# PowerStage.net
KiCad netlist of a schematic drawn in Altium Designer
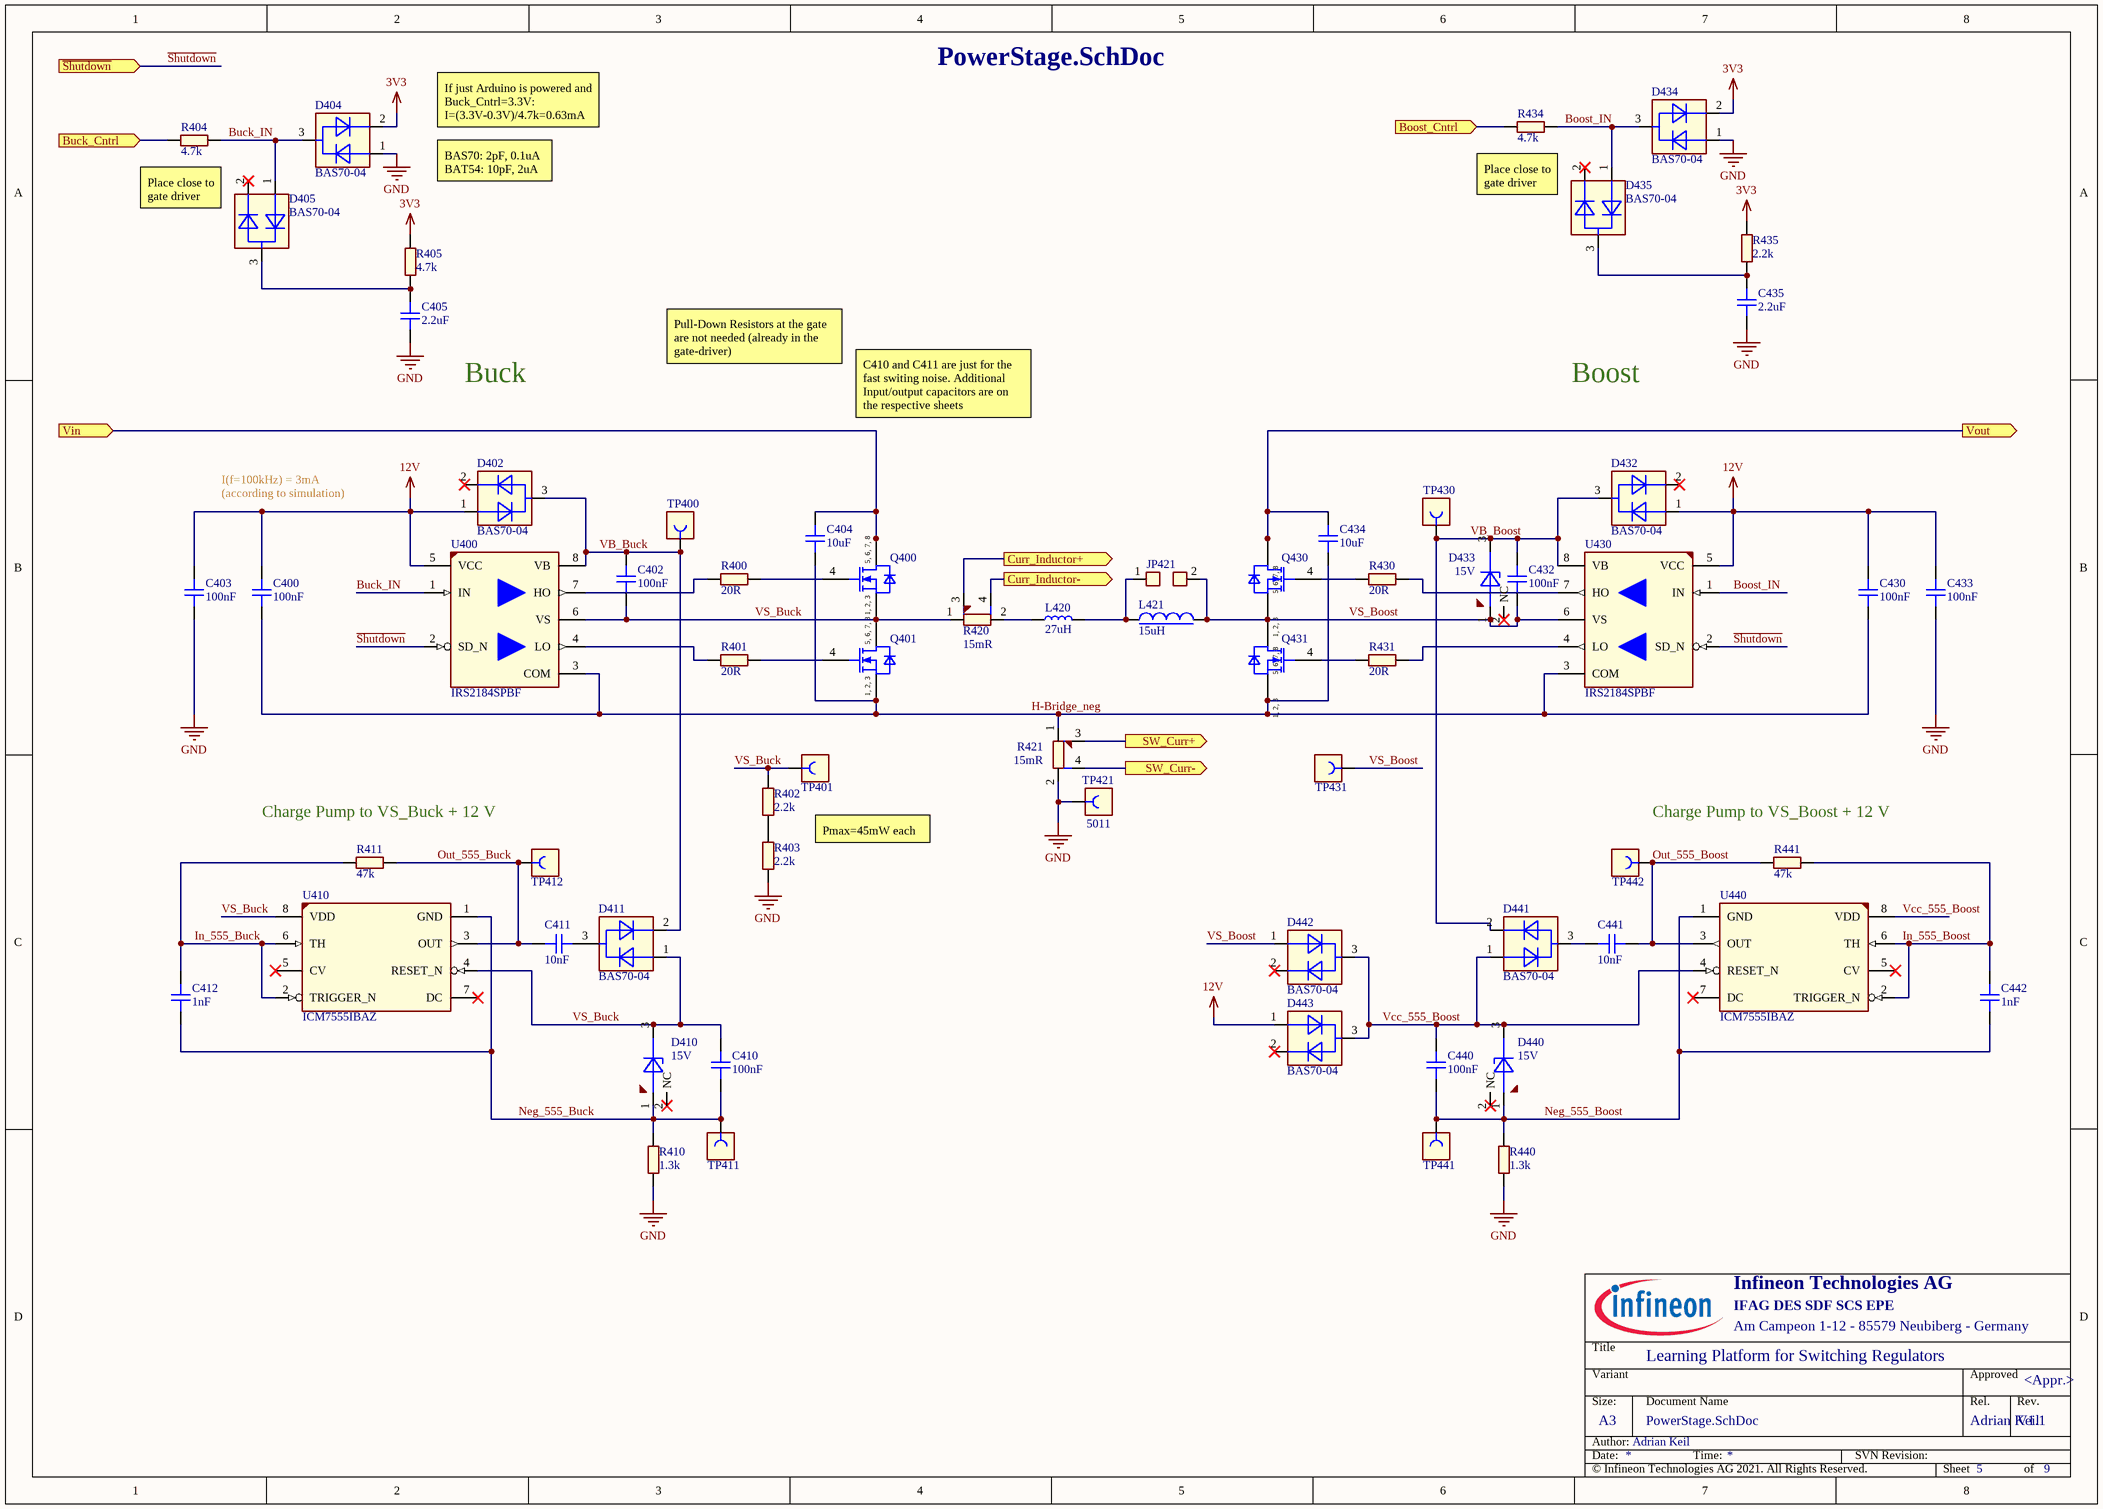
[diagram p0: PowerStage.SchDoc]

(export (version "E")
  (design (tool "Eeschema 10.0.6"))
  (components
    (comp (ref "C400")
      (value "100nF")
      (footprint "CAPC1608X90N-2")
      (description "CAP / CERA / 100nF / 50V / 10% / X7R (EIA) / -55°C to 125°C / 0603 / SMD / -")
      (fields (field (name "MANUFACTURER") "AVX"))
      (libsource (lib "PCBLibraryData") (part "CAP-SGL-STD-02P_00000001"))
    )
    (comp (ref "C402")
      (value "100nF")
      (footprint "CAPC1608X90N-2")
      (description "CAP / CERA / 100nF / 50V / 10% / X7R (EIA) / -55°C to 125°C / 0603 / SMD / -")
      (fields (field (name "MANUFACTURER") "AVX"))
      (libsource (lib "PCBLibraryData") (part "CAP-SGL-STD-02P_00000001"))
    )
    (comp (ref "C403")
      (value "100nF")
      (footprint "CAPC1608X90N-2")
      (description "CAP / CERA / 100nF / 50V / 10% / X7R (EIA) / -55°C to 125°C / 0603 / SMD / -")
      (fields (field (name "MANUFACTURER") "AVX"))
      (libsource (lib "PCBLibraryData") (part "CAP-SGL-STD-02P_00000001"))
    )
    (comp (ref "C404")
      (value "10uF")
      (footprint "CAPC3216X190N-1")
      (description "CAP / CERA / 10uF / 50V / 20% / X5R (EIA) / -55°C to 85°C / 1206 (3216) / SMD / -")
      (fields (field (name "MANUFACTURER") "Taiyo Yuden"))
      (libsource (lib "PCBLibraryData") (part "CAP-SGL-STD-02P_00000001"))
    )
    (comp (ref "C405")
      (value "2.2uF")
      (footprint "CAPC1608X90N-3")
      (description "CAP / CERA / 2.2uF / 25V / 10% / X5R (EIA) / -55°C to 85°C / 0603(1608) / SMD / -")
      (fields (field (name "LEGACY PARTNUMBER") "CAP01010924") (field (name "MANUFACTURER") "MuRata"))
      (libsource (lib "PCBLibraryData") (part "CAP-SGL-STD-02P_00000001"))
    )
    (comp (ref "C410")
      (value "100nF")
      (footprint "CAPC1608X90N-2")
      (description "CAP / CERA / 100nF / 50V / 10% / X7R (EIA) / -55°C to 125°C / 0603 / SMD / -")
      (fields (field (name "MANUFACTURER") "AVX"))
      (libsource (lib "PCBLibraryData") (part "CAP-SGL-STD-02P_00000001"))
    )
    (comp (ref "C411")
      (value "10nF")
      (footprint "CAPC1608X90N-4")
      (description "CAP / CERA / 10nF / 50V / 10% / X8R (EIA) / -55°C to 150°C / 0603(1608) / SMD / -")
      (fields
        (field (name "LEGACY PARTNUMBER") "CAP01010834")
        (field (name "MANUFACTURER") "TDK Corporation")
      )
      (libsource (lib "PCBLibraryData") (part "CAP-SGL-STD-02P_00000001"))
    )
    (comp (ref "C412")
      (value "1nF")
      (footprint "CAPC1608X87N-1")
      (description "CAP / CERA / 1nF / 50V / 10% / X7R (EIA) / -55°C to 125°C / 0603 (1608) / SMD / -")
      (fields (field (name "MANUFACTURER") "Wurth Elektronik"))
      (libsource (lib "PCBLibraryData") (part "CAP-SGL-STD-02P_00000001"))
    )
    (comp (ref "C430")
      (value "100nF")
      (footprint "CAPC1608X90N-2")
      (description "CAP / CERA / 100nF / 50V / 10% / X7R (EIA) / -55°C to 125°C / 0603 / SMD / -")
      (fields (field (name "MANUFACTURER") "AVX"))
      (libsource (lib "PCBLibraryData") (part "CAP-SGL-STD-02P_00000001"))
    )
    (comp (ref "C432")
      (value "100nF")
      (footprint "CAPC1608X90N-2")
      (description "CAP / CERA / 100nF / 50V / 10% / X7R (EIA) / -55°C to 125°C / 0603 / SMD / -")
      (fields (field (name "MANUFACTURER") "AVX"))
      (libsource (lib "PCBLibraryData") (part "CAP-SGL-STD-02P_00000001"))
    )
    (comp (ref "C433")
      (value "100nF")
      (footprint "CAPC1608X90N-2")
      (description "CAP / CERA / 100nF / 50V / 10% / X7R (EIA) / -55°C to 125°C / 0603 / SMD / -")
      (fields (field (name "MANUFACTURER") "AVX"))
      (libsource (lib "PCBLibraryData") (part "CAP-SGL-STD-02P_00000001"))
    )
    (comp (ref "C434")
      (value "10uF")
      (footprint "CAPC3216X190N-1")
      (description "CAP / CERA / 10uF / 50V / 20% / X5R (EIA) / -55°C to 85°C / 1206 (3216) / SMD / -")
      (fields (field (name "MANUFACTURER") "Taiyo Yuden"))
      (libsource (lib "PCBLibraryData") (part "CAP-SGL-STD-02P_00000001"))
    )
    (comp (ref "C435")
      (value "2.2uF")
      (footprint "CAPC1608X90N-3")
      (description "CAP / CERA / 2.2uF / 25V / 10% / X5R (EIA) / -55°C to 85°C / 0603(1608) / SMD / -")
      (fields (field (name "LEGACY PARTNUMBER") "CAP01010924") (field (name "MANUFACTURER") "MuRata"))
      (libsource (lib "PCBLibraryData") (part "CAP-SGL-STD-02P_00000001"))
    )
    (comp (ref "C440")
      (value "100nF")
      (footprint "CAPC1608X90N-2")
      (description "CAP / CERA / 100nF / 50V / 10% / X7R (EIA) / -55°C to 125°C / 0603 / SMD / -")
      (fields (field (name "MANUFACTURER") "AVX"))
      (libsource (lib "PCBLibraryData") (part "CAP-SGL-STD-02P_00000001"))
    )
    (comp (ref "C441")
      (value "10nF")
      (footprint "CAPC1608X90N-4")
      (description "CAP / CERA / 10nF / 50V / 10% / X8R (EIA) / -55°C to 150°C / 0603(1608) / SMD / -")
      (fields
        (field (name "LEGACY PARTNUMBER") "CAP01010834")
        (field (name "MANUFACTURER") "TDK Corporation")
      )
      (libsource (lib "PCBLibraryData") (part "CAP-SGL-STD-02P_00000001"))
    )
    (comp (ref "C442")
      (value "1nF")
      (footprint "CAPC1608X87N-1")
      (description "CAP / CERA / 1nF / 50V / 10% / X7R (EIA) / -55°C to 125°C / 0603 (1608) / SMD / -")
      (fields (field (name "MANUFACTURER") "Wurth Elektronik"))
      (libsource (lib "PCBLibraryData") (part "CAP-SGL-STD-02P_00000001"))
    )
    (comp (ref "D402")
      (value "BAS70-04")
      (footprint "SOT95P240X110-3N-1")
      (description "Silicon Schottky Diode")
      (fields
        (field (name "LEGACY PARTNUMBER") "IFX01400573")
        (field (name "MANUFACTURER") "Infineon Technologies")
      )
      (libsource (lib "PCBLibraryData") (part "d_dual_a1c2ac3_3p"))
    )
    (comp (ref "D404")
      (value "BAS70-04")
      (footprint "SOT95P240X110-3N-1")
      (description "Silicon Schottky Diode")
      (fields
        (field (name "LEGACY PARTNUMBER") "IFX01400573")
        (field (name "MANUFACTURER") "Infineon Technologies")
      )
      (libsource (lib "") (part "d_dual_a1c2ac3_3p_3"))
    )
    (comp (ref "D405")
      (value "BAS70-04")
      (footprint "SOT95P240X110-3N-1")
      (description "Silicon Schottky Diode")
      (fields
        (field (name "LEGACY PARTNUMBER") "IFX01400573")
        (field (name "MANUFACTURER") "Infineon Technologies")
      )
      (libsource (lib "") (part "d_dual_a1c2ac3_3p_1"))
    )
    (comp (ref "D410")
      (value "15V")
      (footprint "SOT95P237X111-3N-1")
      (fields (field (name "MANUFACTURER") "ON Semiconductor"))
      (libsource (lib "PCBLibraryData") (part "d_zener_a1c3_3p"))
    )
    (comp (ref "D411")
      (value "BAS70-04")
      (footprint "SOT95P240X110-3N-1")
      (description "Silicon Schottky Diode")
      (fields
        (field (name "LEGACY PARTNUMBER") "IFX01400573")
        (field (name "MANUFACTURER") "Infineon Technologies")
      )
      (libsource (lib "") (part "d_dual_a1c2ac3_3p_3"))
    )
    (comp (ref "D432")
      (value "BAS70-04")
      (footprint "SOT95P240X110-3N-1")
      (description "Silicon Schottky Diode")
      (fields
        (field (name "LEGACY PARTNUMBER") "IFX01400573")
        (field (name "MANUFACTURER") "Infineon Technologies")
      )
      (libsource (lib "") (part "d_dual_a1c2ac3_3p_3"))
    )
    (comp (ref "D433")
      (value "15V")
      (footprint "SOT95P237X111-3N-1")
      (fields (field (name "MANUFACTURER") "ON Semiconductor"))
      (libsource (lib "PCBLibraryData") (part "d_zener_a1c3_3p"))
    )
    (comp (ref "D434")
      (value "BAS70-04")
      (footprint "SOT95P240X110-3N-1")
      (description "Silicon Schottky Diode")
      (fields
        (field (name "LEGACY PARTNUMBER") "IFX01400573")
        (field (name "MANUFACTURER") "Infineon Technologies")
      )
      (libsource (lib "") (part "d_dual_a1c2ac3_3p_3"))
    )
    (comp (ref "D435")
      (value "BAS70-04")
      (footprint "SOT95P240X110-3N-1")
      (description "Silicon Schottky Diode")
      (fields
        (field (name "LEGACY PARTNUMBER") "IFX01400573")
        (field (name "MANUFACTURER") "Infineon Technologies")
      )
      (libsource (lib "") (part "d_dual_a1c2ac3_3p_1"))
    )
    (comp (ref "D440")
      (value "15V")
      (footprint "SOT95P237X111-3N-1")
      (fields (field (name "MANUFACTURER") "ON Semiconductor"))
      (libsource (lib "PCBLibraryData") (part "d_zener_a1c3_3p"))
    )
    (comp (ref "D441")
      (value "BAS70-04")
      (footprint "SOT95P240X110-3N-1")
      (description "Silicon Schottky Diode")
      (fields
        (field (name "LEGACY PARTNUMBER") "IFX01400573")
        (field (name "MANUFACTURER") "Infineon Technologies")
      )
      (libsource (lib "PCBLibraryData") (part "d_dual_a1c2ac3_3p"))
    )
    (comp (ref "D442")
      (value "BAS70-04")
      (footprint "SOT95P240X110-3N-1")
      (description "Silicon Schottky Diode")
      (fields
        (field (name "LEGACY PARTNUMBER") "IFX01400573")
        (field (name "MANUFACTURER") "Infineon Technologies")
      )
      (libsource (lib "") (part "d_dual_a1c2ac3_3p_2"))
    )
    (comp (ref "D443")
      (value "BAS70-04")
      (footprint "SOT95P240X110-3N-1")
      (description "Silicon Schottky Diode")
      (fields
        (field (name "LEGACY PARTNUMBER") "IFX01400573")
        (field (name "MANUFACTURER") "Infineon Technologies")
      )
      (libsource (lib "") (part "d_dual_a1c2ac3_3p_2"))
    )
    (comp (ref "JP421")
      (value "Solder Jumper 2 Pins")
      (footprint "SOLDER_BRIDGE_0.7X1.299PAD")
      (fields
        (field (name "LEGACY PARTNUMBER") "CON01500959")
        (field (name "MANUFACTURER") "Infineon Technologies")
      )
      (libsource (lib "PCBLibraryData") (part "SJP_2P"))
    )
    (comp (ref "L420")
      (value "27uH")
      (footprint "INDM120120X1000N")
      (fields (field (name "MANUFACTURER") "Wurth Elektronik"))
      (libsource (lib "PCBLibraryData") (part "IND-SGL-STD-02P_00000015"))
    )
    (comp (ref "L421")
      (value "15uH")
      (footprint "IND-SMD-SRP6060FA")
      (fields (field (name "MANUFACTURER") "Bourns"))
      (libsource (lib "PCBLibraryData") (part "IND-SGL-STD-COR-02P_00000016"))
    )
    (comp (ref "Q400")
      (value "igfet_n_ch_enh_dio_1s2s3s4g5d6d7d8d_8p")
      (footprint "INF-PG-TSDSON-8-FL")
      (description "OptiMOS Power - MOSFET, 60 V")
      (fields
        (field (name "LEGACY PARTNUMBER") "IFX01400359")
        (field (name "MANUFACTURER") "Infineon Technologies")
      )
      (libsource (lib "PCBLibraryData") (part "igfet_n_ch_enh_dio_1s2s3s4g5d6d7d8d_8p"))
    )
    (comp (ref "Q401")
      (value "igfet_n_ch_enh_dio_1s2s3s4g5d6d7d8d_8p")
      (footprint "INF-PG-TSDSON-8-FL")
      (description "OptiMOS Power - MOSFET, 60 V")
      (fields
        (field (name "LEGACY PARTNUMBER") "IFX01400359")
        (field (name "MANUFACTURER") "Infineon Technologies")
      )
      (libsource (lib "PCBLibraryData") (part "igfet_n_ch_enh_dio_1s2s3s4g5d6d7d8d_8p"))
    )
    (comp (ref "Q430")
      (value "igfet_n_ch_enh_dio_1s2s3s4g5d6d7d8d_8p")
      (footprint "INF-PG-TSDSON-8-FL")
      (description "OptiMOS Power - MOSFET, 60 V")
      (fields
        (field (name "LEGACY PARTNUMBER") "IFX01400359")
        (field (name "MANUFACTURER") "Infineon Technologies")
      )
      (libsource (lib "PCBLibraryData") (part "igfet_n_ch_enh_dio_1s2s3s4g5d6d7d8d_8p"))
    )
    (comp (ref "Q431")
      (value "igfet_n_ch_enh_dio_1s2s3s4g5d6d7d8d_8p")
      (footprint "INF-PG-TSDSON-8-FL")
      (description "OptiMOS Power - MOSFET, 60 V")
      (fields
        (field (name "LEGACY PARTNUMBER") "IFX01400359")
        (field (name "MANUFACTURER") "Infineon Technologies")
      )
      (libsource (lib "PCBLibraryData") (part "igfet_n_ch_enh_dio_1s2s3s4g5d6d7d8d_8p"))
    )
    (comp (ref "R400")
      (value "20R")
      (footprint "RESC1609X50N")
      (description "RES / STD / 20R / 100mW / 1% / 100ppm/K / -55°C to 155°C / 0603 / SMD / -")
      (fields (field (name "LEGACY PARTNUMBER") "RES01800947") (field (name "MANUFACTURER") "Vishay"))
      (libsource (lib "PCBLibraryData") (part "RES-SGL-STD-02P_00000006"))
    )
    (comp (ref "R401")
      (value "20R")
      (footprint "RESC1609X50N")
      (description "RES / STD / 20R / 100mW / 1% / 100ppm/K / -55°C to 155°C / 0603 / SMD / -")
      (fields (field (name "LEGACY PARTNUMBER") "RES01800947") (field (name "MANUFACTURER") "Vishay"))
      (libsource (lib "PCBLibraryData") (part "RES-SGL-STD-02P_00000006"))
    )
    (comp (ref "R402")
      (value "2.2k")
      (footprint "RESC1609X50N")
      (description "RES / STD / 2.2k / 100mW / 1% / 100ppm/K / -55°C to 155°C / 0603 / SMD / -")
      (fields (field (name "LEGACY PARTNUMBER") "RES01801179") (field (name "MANUFACTURER") "Vishay"))
      (libsource (lib "") (part "RES-SGL-STD-02P_00000006_1"))
    )
    (comp (ref "R403")
      (value "2.2k")
      (footprint "RESC1609X50N")
      (description "RES / STD / 2.2k / 100mW / 1% / 100ppm/K / -55°C to 155°C / 0603 / SMD / -")
      (fields (field (name "LEGACY PARTNUMBER") "RES01801179") (field (name "MANUFACTURER") "Vishay"))
      (libsource (lib "") (part "RES-SGL-STD-02P_00000006_1"))
    )
    (comp (ref "R404")
      (value "4.7k")
      (footprint "RESC1609X50N")
      (description "RES / STD / 4.7k / 100mW / 1% / 100ppm/K / -55°C to 155°C / 0603 / SMD / -")
      (fields (field (name "LEGACY PARTNUMBER") "RES01801219") (field (name "MANUFACTURER") "Vishay"))
      (libsource (lib "") (part "RES-SGL-STD-02P_00000006_3"))
    )
    (comp (ref "R405")
      (value "4.7k")
      (footprint "RESC1609X50N")
      (description "RES / STD / 4.7k / 100mW / 1% / 100ppm/K / -55°C to 155°C / 0603 / SMD / -")
      (fields (field (name "LEGACY PARTNUMBER") "RES01801219") (field (name "MANUFACTURER") "Vishay"))
      (libsource (lib "") (part "RES-SGL-STD-02P_00000006_2"))
    )
    (comp (ref "R410")
      (value "1.3k")
      (footprint "RESC1609X50N")
      (description "RES / STD / 1.3k / 100mW / 1% / 100ppm/K / -55°C to 155°C / 0603 / SMD / -")
      (fields (field (name "LEGACY PARTNUMBER") "RES01801155") (field (name "MANUFACTURER") "Vishay"))
      (libsource (lib "") (part "RES-SGL-STD-02P_00000006_2"))
    )
    (comp (ref "R411")
      (value "47k")
      (footprint "RESC1609X50N")
      (description "RES / STD / 47k / 100mW / 1% / 100ppm/K / -55°C to 155°C / 0603 / SMD / -")
      (fields (field (name "LEGACY PARTNUMBER") "RES01801333") (field (name "MANUFACTURER") "Vishay"))
      (libsource (lib "PCBLibraryData") (part "RES-SGL-STD-02P_00000006"))
    )
    (comp (ref "R420")
      (value "15mR")
      (footprint "RES-SMD-L4T12")
      (description "RES / STD / 15mR / 500mW / 1% / 75ppm/K / -55°C to 155°C / 1206 (3216) / SMD / -")
      (fields (field (name "MANUFACTURER") "Ohmite"))
      (libsource (lib "") (part "RES-SHT-STD-04P_00097BE5_1"))
    )
    (comp (ref "R421")
      (value "15mR")
      (footprint "RES-SMD-L4T12")
      (description "RES / STD / 15mR / 500mW / 1% / 75ppm/K / -55°C to 155°C / 1206 (3216) / SMD / -")
      (fields (field (name "MANUFACTURER") "Ohmite"))
      (libsource (lib "PCBLibraryData") (part "RES-SHT-STD-04P_00097BE5"))
    )
    (comp (ref "R430")
      (value "20R")
      (footprint "RESC1609X50N")
      (description "RES / STD / 20R / 100mW / 1% / 100ppm/K / -55°C to 155°C / 0603 / SMD / -")
      (fields (field (name "LEGACY PARTNUMBER") "RES01800947") (field (name "MANUFACTURER") "Vishay"))
      (libsource (lib "PCBLibraryData") (part "RES-SGL-STD-02P_00000006"))
    )
    (comp (ref "R431")
      (value "20R")
      (footprint "RESC1609X50N")
      (description "RES / STD / 20R / 100mW / 1% / 100ppm/K / -55°C to 155°C / 0603 / SMD / -")
      (fields (field (name "LEGACY PARTNUMBER") "RES01800947") (field (name "MANUFACTURER") "Vishay"))
      (libsource (lib "PCBLibraryData") (part "RES-SGL-STD-02P_00000006"))
    )
    (comp (ref "R434")
      (value "4.7k")
      (footprint "RESC1609X50N")
      (description "RES / STD / 4.7k / 100mW / 1% / 100ppm/K / -55°C to 155°C / 0603 / SMD / -")
      (fields (field (name "LEGACY PARTNUMBER") "RES01801219") (field (name "MANUFACTURER") "Vishay"))
      (libsource (lib "") (part "RES-SGL-STD-02P_00000006_3"))
    )
    (comp (ref "R435")
      (value "2.2k")
      (footprint "RESC1609X50N")
      (description "RES / STD / 2.2k / 100mW / 1% / 100ppm/K / -55°C to 155°C / 0603 / SMD / -")
      (fields (field (name "LEGACY PARTNUMBER") "RES01801179") (field (name "MANUFACTURER") "Vishay"))
      (libsource (lib "") (part "RES-SGL-STD-02P_00000006_1"))
    )
    (comp (ref "R440")
      (value "1.3k")
      (footprint "RESC1609X50N")
      (description "RES / STD / 1.3k / 100mW / 1% / 100ppm/K / -55°C to 155°C / 0603 / SMD / -")
      (fields (field (name "LEGACY PARTNUMBER") "RES01801155") (field (name "MANUFACTURER") "Vishay"))
      (libsource (lib "") (part "RES-SGL-STD-02P_00000006_2"))
    )
    (comp (ref "R441")
      (value "47k")
      (footprint "RESC1609X50N")
      (description "RES / STD / 47k / 100mW / 1% / 100ppm/K / -55°C to 155°C / 0603 / SMD / -")
      (fields (field (name "LEGACY PARTNUMBER") "RES01801333") (field (name "MANUFACTURER") "Vishay"))
      (libsource (lib "") (part "RES-SGL-STD-02P_00000006_2"))
    )
    (comp (ref "TP400")
      (value "S1751-46R")
      (footprint "CON-SMD-TT-S1751-46")
      (description "Test Terminal, Surface Mount (Tape and Reeled Components)")
      (fields (field (name "LEGACY PARTNUMBER") "CON01501015") (field (name "MANUFACTURER") "Harwin"))
      (libsource (lib "") (part "connector_1_f_3"))
    )
    (comp (ref "TP401")
      (value "S1751-46R")
      (footprint "CON-SMD-TT-S1751-46")
      (description "Test Terminal, Surface Mount (Tape and Reeled Components)")
      (fields (field (name "LEGACY PARTNUMBER") "CON01501015") (field (name "MANUFACTURER") "Harwin"))
      (libsource (lib "") (part "connector_1_f_2"))
    )
    (comp (ref "TP411")
      (value "S1751-46R")
      (footprint "CON-SMD-TT-S1751-46")
      (description "Test Terminal, Surface Mount (Tape and Reeled Components)")
      (fields (field (name "LEGACY PARTNUMBER") "CON01501015") (field (name "MANUFACTURER") "Harwin"))
      (libsource (lib "") (part "connector_1_f_1"))
    )
    (comp (ref "TP412")
      (value "S1751-46R")
      (footprint "CON-SMD-TT-S1751-46")
      (description "Test Terminal, Surface Mount (Tape and Reeled Components)")
      (fields (field (name "LEGACY PARTNUMBER") "CON01501015") (field (name "MANUFACTURER") "Harwin"))
      (libsource (lib "") (part "connector_1_f_2"))
    )
    (comp (ref "TP421")
      (value "5011")
      (footprint "CON-THT-TP-5011")
      (description "PC Test Point-Multipurpose THT, Black")
      (fields
        (field (name "LEGACY PARTNUMBER") "CON01500530")
        (field (name "MANUFACTURER") "Keystone Electronics Corp.")
      )
      (libsource (lib "") (part "connector_1_f_4"))
    )
    (comp (ref "TP430")
      (value "S1751-46R")
      (footprint "CON-SMD-TT-S1751-46")
      (description "Test Terminal, Surface Mount (Tape and Reeled Components)")
      (fields (field (name "LEGACY PARTNUMBER") "CON01501015") (field (name "MANUFACTURER") "Harwin"))
      (libsource (lib "") (part "connector_1_f_3"))
    )
    (comp (ref "TP431")
      (value "S1751-46R")
      (footprint "CON-SMD-TT-S1751-46")
      (description "Test Terminal, Surface Mount (Tape and Reeled Components)")
      (fields (field (name "LEGACY PARTNUMBER") "CON01501015") (field (name "MANUFACTURER") "Harwin"))
      (libsource (lib "PCBLibraryData") (part "connector_1_f"))
    )
    (comp (ref "TP441")
      (value "S1751-46R")
      (footprint "CON-SMD-TT-S1751-46")
      (description "Test Terminal, Surface Mount (Tape and Reeled Components)")
      (fields (field (name "LEGACY PARTNUMBER") "CON01501015") (field (name "MANUFACTURER") "Harwin"))
      (libsource (lib "") (part "connector_1_f_1"))
    )
    (comp (ref "TP442")
      (value "S1751-46R")
      (footprint "CON-SMD-TT-S1751-46")
      (description "Test Terminal, Surface Mount (Tape and Reeled Components)")
      (fields (field (name "LEGACY PARTNUMBER") "CON01501015") (field (name "MANUFACTURER") "Harwin"))
      (libsource (lib "PCBLibraryData") (part "connector_1_f"))
    )
    (comp (ref "U400")
      (value "IRS2184SPBF")
      (footprint "SOIC127P600X175-8N-12-V")
      (fields (field (name "MANUFACTURER") "Infineon Technologies"))
      (libsource (lib "") (part "IRS2184S_1"))
    )
    (comp (ref "U410")
      (value "ICM7555IBAZ")
      (footprint "SOIC127P600X175-8N-12")
      (description "General Purpose Timers")
      (fields (field (name "MANUFACTURER") "Renesas"))
      (libsource (lib "") (part "ICM7555_1"))
    )
    (comp (ref "U430")
      (value "IRS2184SPBF")
      (footprint "SOIC127P600X175-8N-12-V")
      (fields (field (name "MANUFACTURER") "Infineon Technologies"))
      (libsource (lib "PCBLibraryData") (part "IRS2184S"))
    )
    (comp (ref "U440")
      (value "ICM7555IBAZ")
      (footprint "SOIC127P600X175-8N-12")
      (description "General Purpose Timers")
      (fields (field (name "MANUFACTURER") "Renesas"))
      (libsource (lib "PCBLibraryData") (part "ICM7555"))
    )
  )
  (nets
    (net (code "2") (name "/Boost_Cntrl") (class "Default")
      (node (ref "R434") (pin "1") (pinfunction "1_1") (pintype "passive"))
    )
    (net (code "3") (name "/Boost_IN") (class "Default")
      (node (ref "D434") (pin "3") (pinfunction "ANODE_/_CATHODE_3") (pintype "passive"))
      (node (ref "D435") (pin "1") (pinfunction "ANODE_1") (pintype "passive"))
      (node (ref "R434") (pin "2") (pinfunction "2_2") (pintype "passive"))
      (node (ref "U430") (pin "1") (pinfunction "IN_1") (pintype "input"))
    )
    (net (code "4") (name "/Buck_Cntrl") (class "Default")
      (node (ref "R404") (pin "1") (pinfunction "1_1") (pintype "passive"))
    )
    (net (code "5") (name "/Buck_IN") (class "Default")
      (node (ref "D404") (pin "3") (pinfunction "ANODE_/_CATHODE_3") (pintype "passive"))
      (node (ref "D405") (pin "1") (pinfunction "ANODE_1") (pintype "passive"))
      (node (ref "R404") (pin "2") (pinfunction "2_2") (pintype "passive"))
      (node (ref "U400") (pin "1") (pinfunction "IN_1") (pintype "input"))
    )
    (net (code "6") (name "/Curr_Inductor+") (class "Default")
      (node (ref "R420") (pin "3") (pinfunction "I1_3") (pintype "passive"))
    )
    (net (code "7") (name "/Curr_Inductor-") (class "Default")
      (node (ref "R420") (pin "4") (pinfunction "I2_4") (pintype "passive"))
    )
    (net (code "8") (name "/H-Bridge_neg") (class "Default")
      (node (ref "C400") (pin "1") (pinfunction "1_1") (pintype "passive"))
      (node (ref "C404") (pin "1") (pinfunction "1_1") (pintype "passive"))
      (node (ref "C430") (pin "1") (pinfunction "1_1") (pintype "passive"))
      (node (ref "C434") (pin "1") (pinfunction "1_1") (pintype "passive"))
      (node (ref "Q401") (pin "1") (pinfunction "SOURCE_1") (pintype "passive"))
      (node (ref "Q401") (pin "2") (pinfunction "SOURCE_2") (pintype "passive"))
      (node (ref "Q401") (pin "3") (pinfunction "SOURCE_3") (pintype "passive"))
      (node (ref "Q431") (pin "1") (pinfunction "SOURCE_1") (pintype "passive"))
      (node (ref "Q431") (pin "2") (pinfunction "SOURCE_2") (pintype "passive"))
      (node (ref "Q431") (pin "3") (pinfunction "SOURCE_3") (pintype "passive"))
      (node (ref "R421") (pin "1") (pinfunction "V1_1") (pintype "passive"))
      (node (ref "U400") (pin "3") (pinfunction "COM_3") (pintype "passive"))
      (node (ref "U430") (pin "3") (pinfunction "COM_3") (pintype "passive"))
    )
    (net (code "9") (name "/In_555_Boost") (class "Default")
      (node (ref "C442") (pin "2") (pinfunction "2_2") (pintype "passive"))
      (node (ref "R441") (pin "2") (pinfunction "2_2") (pintype "passive"))
      (node (ref "U440") (pin "2") (pinfunction "TRIGGER_N_2") (pintype "input"))
      (node (ref "U440") (pin "6") (pinfunction "TH_6") (pintype "input"))
    )
    (net (code "10") (name "/In_555_Buck") (class "Default")
      (node (ref "C412") (pin "2") (pinfunction "2_2") (pintype "passive"))
      (node (ref "R411") (pin "2") (pinfunction "2_2") (pintype "passive"))
      (node (ref "U410") (pin "2") (pinfunction "TRIGGER_N_2") (pintype "input"))
      (node (ref "U410") (pin "6") (pinfunction "TH_6") (pintype "input"))
    )
    (net (code "11") (name "/Neg_555_Boost") (class "Default")
      (node (ref "C440") (pin "1") (pinfunction "1_1") (pintype "passive"))
      (node (ref "C442") (pin "1") (pinfunction "1_1") (pintype "passive"))
      (node (ref "D440") (pin "1") (pinfunction "ANODE_1") (pintype "passive"))
      (node (ref "R440") (pin "2") (pinfunction "2_2") (pintype "passive"))
      (node (ref "TP441") (pin "1") (pinfunction "1_1") (pintype "passive"))
      (node (ref "U440") (pin "1") (pinfunction "GND_1") (pintype "power_in"))
    )
    (net (code "12") (name "/Neg_555_Buck") (class "Default")
      (node (ref "C410") (pin "1") (pinfunction "1_1") (pintype "passive"))
      (node (ref "C412") (pin "1") (pinfunction "1_1") (pintype "passive"))
      (node (ref "D410") (pin "1") (pinfunction "ANODE_1") (pintype "passive"))
      (node (ref "R410") (pin "2") (pinfunction "2_2") (pintype "passive"))
      (node (ref "TP411") (pin "1") (pinfunction "1_1") (pintype "passive"))
      (node (ref "U410") (pin "1") (pinfunction "GND_1") (pintype "power_in"))
    )
    (net (code "13") (name "/Out_555_Boost") (class "Default")
      (node (ref "C441") (pin "1") (pinfunction "1_1") (pintype "passive"))
      (node (ref "R441") (pin "1") (pinfunction "1_1") (pintype "passive"))
      (node (ref "TP442") (pin "1") (pinfunction "1_1") (pintype "passive"))
      (node (ref "U440") (pin "3") (pinfunction "OUT_3") (pintype "output"))
    )
    (net (code "14") (name "/Out_555_Buck") (class "Default")
      (node (ref "C411") (pin "2") (pinfunction "2_2") (pintype "passive"))
      (node (ref "R411") (pin "1") (pinfunction "1_1") (pintype "passive"))
      (node (ref "TP412") (pin "1") (pinfunction "1_1") (pintype "passive"))
      (node (ref "U410") (pin "3") (pinfunction "OUT_3") (pintype "output"))
    )
    (net (code "15") (name "/SW_Curr+") (class "Default")
      (node (ref "R421") (pin "3") (pinfunction "I1_3") (pintype "passive"))
    )
    (net (code "16") (name "/SW_Curr-") (class "Default")
      (node (ref "R421") (pin "4") (pinfunction "I2_4") (pintype "passive"))
    )
    (net (code "17") (name "/Shutdown") (class "Default")
      (node (ref "U400") (pin "2") (pinfunction "SD_N_2") (pintype "input"))
      (node (ref "U430") (pin "2") (pinfunction "SD_N_2") (pintype "input"))
    )
    (net (code "18") (name "/VB_Boost") (class "Default")
      (node (ref "C432") (pin "2") (pinfunction "2_2") (pintype "passive"))
      (node (ref "D432") (pin "3") (pinfunction "ANODE_/_CATHODE_3") (pintype "passive"))
      (node (ref "D433") (pin "3") (pinfunction "CATHODE_3") (pintype "passive"))
      (node (ref "D441") (pin "2") (pinfunction "CATHODE_2") (pintype "passive"))
      (node (ref "TP430") (pin "1") (pinfunction "1_1") (pintype "passive"))
      (node (ref "U430") (pin "8") (pinfunction "VB_8") (pintype "power_in"))
    )
    (net (code "19") (name "/VB_Buck") (class "Default")
      (node (ref "C402") (pin "2") (pinfunction "2_2") (pintype "passive"))
      (node (ref "D402") (pin "3") (pinfunction "ANODE_/_CATHODE_3") (pintype "passive"))
      (node (ref "D411") (pin "2") (pinfunction "CATHODE_2") (pintype "passive"))
      (node (ref "TP400") (pin "1") (pinfunction "1_1") (pintype "passive"))
      (node (ref "U400") (pin "8") (pinfunction "VB_8") (pintype "power_in"))
    )
    (net (code "20") (name "/VS_Boost") (class "Default")
      (node (ref "C432") (pin "1") (pinfunction "1_1") (pintype "passive"))
      (node (ref "D433") (pin "1") (pinfunction "ANODE_1") (pintype "passive"))
      (node (ref "D442") (pin "1") (pinfunction "ANODE_1") (pintype "passive"))
      (node (ref "JP421") (pin "2") (pinfunction "2_2") (pintype "passive"))
      (node (ref "L421") (pin "2") (pinfunction "2_2") (pintype "passive"))
      (node (ref "Q430") (pin "1") (pinfunction "SOURCE_1") (pintype "passive"))
      (node (ref "Q430") (pin "2") (pinfunction "SOURCE_2") (pintype "passive"))
      (node (ref "Q430") (pin "3") (pinfunction "SOURCE_3") (pintype "passive"))
      (node (ref "Q431") (pin "5") (pinfunction "DRAIN_5") (pintype "passive"))
      (node (ref "Q431") (pin "6") (pinfunction "DRAIN_6") (pintype "passive"))
      (node (ref "Q431") (pin "7") (pinfunction "DRAIN_7") (pintype "passive"))
      (node (ref "Q431") (pin "8") (pinfunction "DRAIN_8") (pintype "passive"))
      (node (ref "TP431") (pin "1") (pinfunction "1_1") (pintype "passive"))
      (node (ref "U430") (pin "6") (pinfunction "VS_6") (pintype "power_in"))
    )
    (net (code "21") (name "/VS_Buck") (class "Default")
      (node (ref "C402") (pin "1") (pinfunction "1_1") (pintype "passive"))
      (node (ref "C410") (pin "2") (pinfunction "2_2") (pintype "passive"))
      (node (ref "D410") (pin "3") (pinfunction "CATHODE_3") (pintype "passive"))
      (node (ref "D411") (pin "1") (pinfunction "ANODE_1") (pintype "passive"))
      (node (ref "Q400") (pin "1") (pinfunction "SOURCE_1") (pintype "passive"))
      (node (ref "Q400") (pin "2") (pinfunction "SOURCE_2") (pintype "passive"))
      (node (ref "Q400") (pin "3") (pinfunction "SOURCE_3") (pintype "passive"))
      (node (ref "Q401") (pin "5") (pinfunction "DRAIN_5") (pintype "passive"))
      (node (ref "Q401") (pin "6") (pinfunction "DRAIN_6") (pintype "passive"))
      (node (ref "Q401") (pin "7") (pinfunction "DRAIN_7") (pintype "passive"))
      (node (ref "Q401") (pin "8") (pinfunction "DRAIN_8") (pintype "passive"))
      (node (ref "R402") (pin "1") (pinfunction "1_1") (pintype "passive"))
      (node (ref "R420") (pin "1") (pinfunction "V1_1") (pintype "passive"))
      (node (ref "TP401") (pin "1") (pinfunction "1_1") (pintype "passive"))
      (node (ref "U400") (pin "6") (pinfunction "VS_6") (pintype "power_in"))
      (node (ref "U410") (pin "4") (pinfunction "RESET_N_4") (pintype "input"))
      (node (ref "U410") (pin "8") (pinfunction "VDD_8") (pintype "power_in"))
    )
    (net (code "22") (name "/Vcc_555_Boost") (class "Default")
      (node (ref "C440") (pin "2") (pinfunction "2_2") (pintype "passive"))
      (node (ref "D440") (pin "3") (pinfunction "CATHODE_3") (pintype "passive"))
      (node (ref "D441") (pin "1") (pinfunction "ANODE_1") (pintype "passive"))
      (node (ref "D442") (pin "3") (pinfunction "ANODE_/_CATHODE_3") (pintype "passive"))
      (node (ref "D443") (pin "3") (pinfunction "ANODE_/_CATHODE_3") (pintype "passive"))
      (node (ref "U440") (pin "4") (pinfunction "RESET_N_4") (pintype "input"))
      (node (ref "U440") (pin "8") (pinfunction "VDD_8") (pintype "power_in"))
    )
    (net (code "23") (name "/Vin") (class "Default")
      (node (ref "C404") (pin "2") (pinfunction "2_2") (pintype "passive"))
      (node (ref "Q400") (pin "5") (pinfunction "DRAIN_5") (pintype "passive"))
      (node (ref "Q400") (pin "6") (pinfunction "DRAIN_6") (pintype "passive"))
      (node (ref "Q400") (pin "7") (pinfunction "DRAIN_7") (pintype "passive"))
      (node (ref "Q400") (pin "8") (pinfunction "DRAIN_8") (pintype "passive"))
    )
    (net (code "24") (name "/Vout") (class "Default")
      (node (ref "C434") (pin "2") (pinfunction "2_2") (pintype "passive"))
      (node (ref "Q430") (pin "5") (pinfunction "DRAIN_5") (pintype "passive"))
      (node (ref "Q430") (pin "6") (pinfunction "DRAIN_6") (pintype "passive"))
      (node (ref "Q430") (pin "7") (pinfunction "DRAIN_7") (pintype "passive"))
      (node (ref "Q430") (pin "8") (pinfunction "DRAIN_8") (pintype "passive"))
    )
    (net (code "25") (name "3V3") (class "Default")
      (node (ref "D404") (pin "2") (pinfunction "CATHODE_2") (pintype "passive"))
      (node (ref "D434") (pin "2") (pinfunction "CATHODE_2") (pintype "passive"))
      (node (ref "R405") (pin "2") (pinfunction "2_2") (pintype "passive"))
      (node (ref "R435") (pin "1") (pinfunction "1_1") (pintype "passive"))
    )
    (net (code "26") (name "12V") (class "Default")
      (node (ref "C400") (pin "2") (pinfunction "2_2") (pintype "passive"))
      (node (ref "C403") (pin "2") (pinfunction "2_2") (pintype "passive"))
      (node (ref "C430") (pin "2") (pinfunction "2_2") (pintype "passive"))
      (node (ref "C433") (pin "2") (pinfunction "2_2") (pintype "passive"))
      (node (ref "D402") (pin "1") (pinfunction "ANODE_1") (pintype "passive"))
      (node (ref "D432") (pin "1") (pinfunction "ANODE_1") (pintype "passive"))
      (node (ref "D443") (pin "1") (pinfunction "ANODE_1") (pintype "passive"))
      (node (ref "U400") (pin "5") (pinfunction "VCC_5") (pintype "power_in"))
      (node (ref "U430") (pin "5") (pinfunction "VCC_5") (pintype "power_in"))
    )
    (net (code "27") (name "GND") (class "Default")
      (node (ref "C403") (pin "1") (pinfunction "1_1") (pintype "passive"))
      (node (ref "C405") (pin "1") (pinfunction "1_1") (pintype "passive"))
      (node (ref "C433") (pin "1") (pinfunction "1_1") (pintype "passive"))
      (node (ref "C435") (pin "1") (pinfunction "1_1") (pintype "passive"))
      (node (ref "D404") (pin "1") (pinfunction "ANODE_1") (pintype "passive"))
      (node (ref "D434") (pin "1") (pinfunction "ANODE_1") (pintype "passive"))
      (node (ref "R403") (pin "2") (pinfunction "2_2") (pintype "passive"))
      (node (ref "R410") (pin "1") (pinfunction "1_1") (pintype "passive"))
      (node (ref "R421") (pin "2") (pinfunction "V2_2") (pintype "passive"))
      (node (ref "R440") (pin "1") (pinfunction "1_1") (pintype "passive"))
      (node (ref "TP421") (pin "1") (pinfunction "1_1") (pintype "passive"))
    )
    (net (code "28") (name "Net-(D405-ANODE_{slash}_CATHODE)") (class "Default")
      (node (ref "C405") (pin "2") (pinfunction "2_2") (pintype "passive"))
      (node (ref "D405") (pin "3") (pinfunction "ANODE_/_CATHODE_3") (pintype "passive"))
      (node (ref "R405") (pin "1") (pinfunction "1_1") (pintype "passive"))
    )
    (net (code "29") (name "Net-(D411-ANODE_{slash}_CATHODE)") (class "Default")
      (node (ref "C411") (pin "1") (pinfunction "1_1") (pintype "passive"))
      (node (ref "D411") (pin "3") (pinfunction "ANODE_/_CATHODE_3") (pintype "passive"))
    )
    (net (code "30") (name "Net-(D435-ANODE_{slash}_CATHODE)") (class "Default")
      (node (ref "C435") (pin "2") (pinfunction "2_2") (pintype "passive"))
      (node (ref "D435") (pin "3") (pinfunction "ANODE_/_CATHODE_3") (pintype "passive"))
      (node (ref "R435") (pin "2") (pinfunction "2_2") (pintype "passive"))
    )
    (net (code "31") (name "Net-(D441-ANODE_{slash}_CATHODE)") (class "Default")
      (node (ref "C441") (pin "2") (pinfunction "2_2") (pintype "passive"))
      (node (ref "D441") (pin "3") (pinfunction "ANODE_/_CATHODE_3") (pintype "passive"))
    )
    (net (code "32") (name "Net-(JP421-Pad1)") (class "Default")
      (node (ref "JP421") (pin "1") (pinfunction "1_1") (pintype "passive"))
      (node (ref "L420") (pin "2") (pinfunction "2_2") (pintype "passive"))
      (node (ref "L421") (pin "1") (pinfunction "1_1") (pintype "passive"))
    )
    (net (code "33") (name "Net-(Q400-GATE)") (class "Default")
      (node (ref "Q400") (pin "4") (pinfunction "GATE_4") (pintype "passive"))
      (node (ref "R400") (pin "1") (pinfunction "1_1") (pintype "passive"))
    )
    (net (code "34") (name "Net-(Q401-GATE)") (class "Default")
      (node (ref "Q401") (pin "4") (pinfunction "GATE_4") (pintype "passive"))
      (node (ref "R401") (pin "1") (pinfunction "1_1") (pintype "passive"))
    )
    (net (code "35") (name "Net-(Q430-GATE)") (class "Default")
      (node (ref "Q430") (pin "4") (pinfunction "GATE_4") (pintype "passive"))
      (node (ref "R430") (pin "2") (pinfunction "2_2") (pintype "passive"))
    )
    (net (code "36") (name "Net-(Q431-GATE)") (class "Default")
      (node (ref "Q431") (pin "4") (pinfunction "GATE_4") (pintype "passive"))
      (node (ref "R431") (pin "2") (pinfunction "2_2") (pintype "passive"))
    )
    (net (code "37") (name "Net-(R402-Pad2)") (class "Default")
      (node (ref "R402") (pin "2") (pinfunction "2_2") (pintype "passive"))
      (node (ref "R403") (pin "1") (pinfunction "1_1") (pintype "passive"))
    )
    (net (code "38") (name "Net-(R420-V2)") (class "Default")
      (node (ref "L420") (pin "1") (pinfunction "1_1") (pintype "passive"))
      (node (ref "R420") (pin "2") (pinfunction "V2_2") (pintype "passive"))
    )
    (net (code "39") (name "Net-(U400-HO)") (class "Default")
      (node (ref "R400") (pin "2") (pinfunction "2_2") (pintype "passive"))
      (node (ref "U400") (pin "7") (pinfunction "HO_7") (pintype "output"))
    )
    (net (code "40") (name "Net-(U400-LO)") (class "Default")
      (node (ref "R401") (pin "2") (pinfunction "2_2") (pintype "passive"))
      (node (ref "U400") (pin "4") (pinfunction "LO_4") (pintype "output"))
    )
    (net (code "41") (name "Net-(U430-HO)") (class "Default")
      (node (ref "R430") (pin "1") (pinfunction "1_1") (pintype "passive"))
      (node (ref "U430") (pin "7") (pinfunction "HO_7") (pintype "output"))
    )
    (net (code "42") (name "Net-(U430-LO)") (class "Default")
      (node (ref "R431") (pin "1") (pinfunction "1_1") (pintype "passive"))
      (node (ref "U430") (pin "4") (pinfunction "LO_4") (pintype "output"))
    )
    (net (code "43") (name "unconnected-(D402-CATHODE-Pad2)") (class "Default")
      (node (ref "D402") (pin "2") (pinfunction "CATHODE_2") (pintype "passive+no_connect"))
    )
    (net (code "44") (name "unconnected-(D405-CATHODE-Pad2)") (class "Default")
      (node (ref "D405") (pin "2") (pinfunction "CATHODE_2") (pintype "passive+no_connect"))
    )
    (net (code "45") (name "unconnected-(D410-NC-Pad2)") (class "Default")
      (node (ref "D410") (pin "2") (pinfunction "NC_2") (pintype "passive+no_connect"))
    )
    (net (code "46") (name "unconnected-(D432-CATHODE-Pad2)") (class "Default")
      (node (ref "D432") (pin "2") (pinfunction "CATHODE_2") (pintype "passive+no_connect"))
    )
    (net (code "47") (name "unconnected-(D433-NC-Pad2)") (class "Default")
      (node (ref "D433") (pin "2") (pinfunction "NC_2") (pintype "passive+no_connect"))
    )
    (net (code "48") (name "unconnected-(D435-CATHODE-Pad2)") (class "Default")
      (node (ref "D435") (pin "2") (pinfunction "CATHODE_2") (pintype "passive+no_connect"))
    )
    (net (code "49") (name "unconnected-(D440-NC-Pad2)") (class "Default")
      (node (ref "D440") (pin "2") (pinfunction "NC_2") (pintype "passive+no_connect"))
    )
    (net (code "50") (name "unconnected-(D442-CATHODE-Pad2)") (class "Default")
      (node (ref "D442") (pin "2") (pinfunction "CATHODE_2") (pintype "passive+no_connect"))
    )
    (net (code "51") (name "unconnected-(D443-CATHODE-Pad2)") (class "Default")
      (node (ref "D443") (pin "2") (pinfunction "CATHODE_2") (pintype "passive+no_connect"))
    )
    (net (code "52") (name "unconnected-(U410-CV-Pad5)") (class "Default")
      (node (ref "U410") (pin "5") (pinfunction "CV_5") (pintype "power_in+no_connect"))
    )
    (net (code "53") (name "unconnected-(U410-DC-Pad7)") (class "Default")
      (node (ref "U410") (pin "7") (pinfunction "DC_7") (pintype "passive+no_connect"))
    )
    (net (code "54") (name "unconnected-(U440-CV-Pad5)") (class "Default")
      (node (ref "U440") (pin "5") (pinfunction "CV_5") (pintype "power_in+no_connect"))
    )
    (net (code "55") (name "unconnected-(U440-DC-Pad7)") (class "Default")
      (node (ref "U440") (pin "7") (pinfunction "DC_7") (pintype "passive+no_connect"))
    )
  )
)
